# main.net
KiCad netlist of a schematic drawn in EAGLE
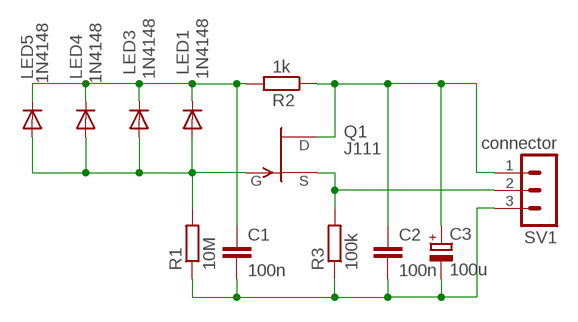
[diagram p0: schematic, sheet 1]

(export (version "E")
  (design (tool "Eeschema 10.0.6"))
  (components
    (comp (ref "C1")
      (value "100n")
      (footprint "eagle-import:C1206")
      (libsource (lib "eagle-import") (part "C-EUC1206"))
    )
    (comp (ref "C2")
      (value "100n")
      (footprint "eagle-import:C1206")
      (libsource (lib "eagle-import") (part "C-EUC1206"))
    )
    (comp (ref "C3")
      (value "100u")
      (footprint "eagle-import:SMC_C")
      (libsource (lib "eagle-import") (part "CPOL-EUSMCC"))
    )
    (comp (ref "LED1")
      (value "1N4148")
      (footprint "eagle-import:DO35-7")
      (libsource (lib "eagle-import") (part "1N4148DO35-7"))
    )
    (comp (ref "LED3")
      (value "1N4148")
      (footprint "eagle-import:DO35-7")
      (libsource (lib "eagle-import") (part "1N4148DO35-7"))
    )
    (comp (ref "LED4")
      (value "1N4148")
      (footprint "eagle-import:DO35-7")
      (libsource (lib "eagle-import") (part "1N4148DO35-7"))
    )
    (comp (ref "LED5")
      (value "1N4148")
      (footprint "eagle-import:DO35-7")
      (libsource (lib "eagle-import") (part "1N4148DO35-7"))
    )
    (comp (ref "Q1")
      (value "J111")
      (footprint "eagle-import:SOT23")
      (libsource (lib "eagle-import") (part "?20SST1"))
    )
    (comp (ref "R1")
      (value "10M")
      (footprint "eagle-import:0207_10")
      (libsource (lib "eagle-import") (part "R-EU_0207/10"))
    )
    (comp (ref "R2")
      (value "1k")
      (footprint "eagle-import:R1206")
      (libsource (lib "eagle-import") (part "R-EU_R1206"))
    )
    (comp (ref "R3")
      (value "100k")
      (footprint "eagle-import:R1206")
      (libsource (lib "eagle-import") (part "R-EU_R1206"))
    )
    (comp (ref "SV1")
      (value "connector")
      (footprint "eagle-import:MA03-1")
      (libsource (lib "eagle-import") (part "MA03-1"))
    )
  )
  (nets
    (net (code "1") (name "Net-(C1-Pad1)") (class "Default")
      (node (ref "C1") (pin "1") (pinfunction "1_1") (pintype "passive"))
      (node (ref "LED1") (pin "C") (pinfunction "C_C") (pintype "passive"))
      (node (ref "LED3") (pin "C") (pinfunction "C_C") (pintype "passive"))
      (node (ref "LED4") (pin "C") (pinfunction "C_C") (pintype "passive"))
      (node (ref "LED5") (pin "C") (pinfunction "C_C") (pintype "passive"))
      (node (ref "R2") (pin "2") (pinfunction "2_2") (pintype "passive"))
    )
    (net (code "2") (name "Net-(C1-Pad2)") (class "Default")
      (node (ref "C1") (pin "2") (pinfunction "2_2") (pintype "passive"))
      (node (ref "C2") (pin "2") (pinfunction "2_2") (pintype "passive"))
      (node (ref "C3") (pin "-") (pinfunction "-_-") (pintype "passive"))
      (node (ref "R1") (pin "1") (pinfunction "1_1") (pintype "passive"))
      (node (ref "R3") (pin "1") (pinfunction "1_1") (pintype "passive"))
      (node (ref "SV1") (pin "3") (pinfunction "3_3") (pintype "passive"))
    )
    (net (code "3") (name "Net-(Q1-D)") (class "Default")
      (node (ref "C2") (pin "1") (pinfunction "1_1") (pintype "passive"))
      (node (ref "C3") (pin "+") (pinfunction "+_+") (pintype "passive"))
      (node (ref "Q1") (pin "1") (pinfunction "D_1") (pintype "passive"))
      (node (ref "R2") (pin "1") (pinfunction "1_1") (pintype "passive"))
      (node (ref "SV1") (pin "1") (pinfunction "1_1") (pintype "passive"))
    )
    (net (code "4") (name "Net-(Q1-G)") (class "Default")
      (node (ref "LED1") (pin "A") (pinfunction "A_A") (pintype "passive"))
      (node (ref "LED3") (pin "A") (pinfunction "A_A") (pintype "passive"))
      (node (ref "LED4") (pin "A") (pinfunction "A_A") (pintype "passive"))
      (node (ref "LED5") (pin "A") (pinfunction "A_A") (pintype "passive"))
      (node (ref "Q1") (pin "3") (pinfunction "G_3") (pintype "passive"))
      (node (ref "R1") (pin "2") (pinfunction "2_2") (pintype "passive"))
    )
    (net (code "5") (name "Net-(Q1-S)") (class "Default")
      (node (ref "Q1") (pin "2") (pinfunction "S_2") (pintype "passive"))
      (node (ref "R3") (pin "2") (pinfunction "2_2") (pintype "passive"))
      (node (ref "SV1") (pin "2") (pinfunction "2_2") (pintype "passive"))
    )
  )
)
